# encoder.net
KiCad netlist of a schematic drawn in EAGLE
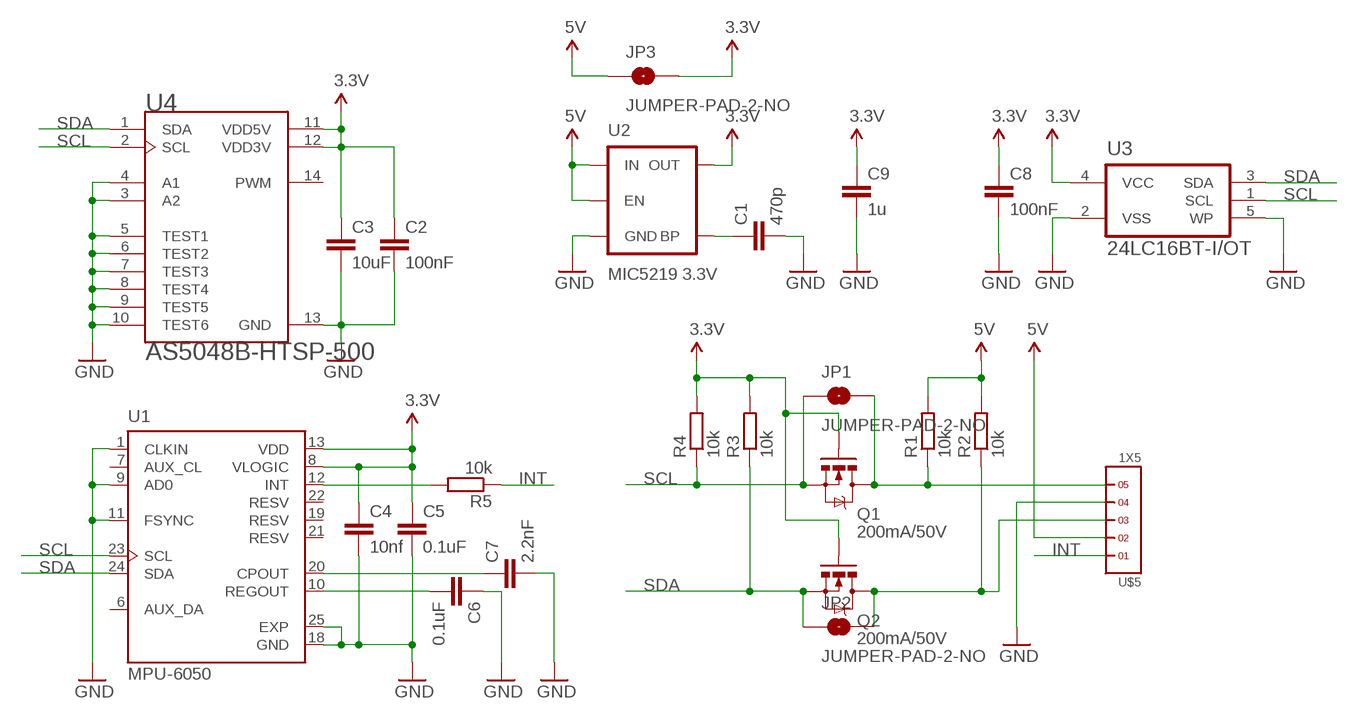
[diagram p0: schematic, sheet 1]

(export (version "E")
  (design (tool "Eeschema 10.0.6"))
  (components
    (comp (ref "C1")
      (value "470p")
      (footprint "eagle-import:C0402K")
      (libsource (lib "eagle-import") (part "C-EUC0402K"))
    )
    (comp (ref "C2")
      (value "100nF")
      (footprint "eagle-import:C0402K")
      (libsource (lib "eagle-import") (part "C-EUC0402K"))
    )
    (comp (ref "C3")
      (value "10uF")
      (footprint "eagle-import:C0603K")
      (libsource (lib "eagle-import") (part "C-EUC0603K"))
    )
    (comp (ref "C4")
      (value "10nf")
      (footprint "eagle-import:C0402K")
      (libsource (lib "eagle-import") (part "C-EUC0402K"))
    )
    (comp (ref "C5")
      (value "0.1uF")
      (footprint "eagle-import:C0402K")
      (libsource (lib "eagle-import") (part "C-EUC0402K"))
    )
    (comp (ref "C6")
      (value "0.1uF")
      (footprint "eagle-import:C0402K")
      (libsource (lib "eagle-import") (part "C-EUC0402K"))
    )
    (comp (ref "C7")
      (value "2.2nF")
      (footprint "eagle-import:C0402K")
      (libsource (lib "eagle-import") (part "C-EUC0402K"))
    )
    (comp (ref "C8")
      (value "100nF")
      (footprint "eagle-import:C0402K")
      (libsource (lib "eagle-import") (part "C-EUC0402K"))
    )
    (comp (ref "C9")
      (value "1u")
      (footprint "eagle-import:C0402K")
      (libsource (lib "eagle-import") (part "C-EUC0402K"))
    )
    (comp (ref "JP1")
      (value "JUMPER-PAD-2-NO")
      (footprint "eagle-import:PAD-JUMPER-2-NO_NO_SILK")
      (libsource (lib "eagle-import") (part "JUMPER-PAD-2-NO"))
    )
    (comp (ref "JP2")
      (value "JUMPER-PAD-2-NO")
      (footprint "eagle-import:PAD-JUMPER-2-NO_NO_SILK")
      (libsource (lib "eagle-import") (part "JUMPER-PAD-2-NO"))
    )
    (comp (ref "JP3")
      (value "JUMPER-PAD-2-NO")
      (footprint "eagle-import:PAD-JUMPER-2-NO_NO_SILK")
      (libsource (lib "eagle-import") (part "JUMPER-PAD-2-NO"))
    )
    (comp (ref "Q1")
      (value "200mA/50V")
      (footprint "eagle-import:SOT23-3")
      (libsource (lib "eagle-import") (part "MOSFET-NCHANNELBSS138"))
    )
    (comp (ref "Q2")
      (value "200mA/50V")
      (footprint "eagle-import:SOT23-3")
      (libsource (lib "eagle-import") (part "MOSFET-NCHANNELBSS138"))
    )
    (comp (ref "R1")
      (value "10k")
      (footprint "eagle-import:R0402")
      (libsource (lib "eagle-import") (part "R-EU_R0402"))
    )
    (comp (ref "R2")
      (value "10k")
      (footprint "eagle-import:R0402")
      (libsource (lib "eagle-import") (part "R-EU_R0402"))
    )
    (comp (ref "R3")
      (value "10k")
      (footprint "eagle-import:R0402")
      (libsource (lib "eagle-import") (part "R-EU_R0402"))
    )
    (comp (ref "R4")
      (value "10k")
      (footprint "eagle-import:R0402")
      (libsource (lib "eagle-import") (part "R-EU_R0402"))
    )
    (comp (ref "R5")
      (value "10k")
      (footprint "eagle-import:R0402")
      (libsource (lib "eagle-import") (part "R-EU_R0402"))
    )
    (comp (ref "U$5")
      (value "1X5")
      (footprint "eagle-import:1X5")
      (libsource (lib "eagle-import") (part "1X5"))
    )
    (comp (ref "U1")
      (value "MPU-6050")
      (footprint "eagle-import:QFN50P400X400X95-25N")
      (libsource (lib "eagle-import") (part "MPU-6050"))
    )
    (comp (ref "U2")
      (value "MIC5219 3.3V")
      (footprint "eagle-import:SOT23-5")
      (libsource (lib "eagle-import") (part "V_REG_MIC52193.3V"))
    )
    (comp (ref "U3")
      (value "24LC16BT-I/OT")
      (footprint "eagle-import:SOT-23-5")
      (libsource (lib "eagle-import") (part "24LC16BT-I/OT"))
    )
    (comp (ref "U4")
      (value "AS5048B-HTSP-500")
      (footprint "eagle-import:SOP65P640X120-14N")
      (libsource (lib "eagle-import") (part "AS5048B-HTSP-500"))
    )
  )
  (nets
    (net (code "1") (name "/INT") (class "Default")
      (node (ref "R5") (pin "1") (pinfunction "1_1") (pintype "passive"))
      (node (ref "U$5") (pin "1") (pinfunction "1_1") (pintype "bidirectional"))
    )
    (net (code "2") (name "/SCL") (class "Default")
      (node (ref "JP1") (pin "1") (pinfunction "1_1") (pintype "passive"))
      (node (ref "Q1") (pin "2") (pinfunction "S_2") (pintype "passive"))
      (node (ref "R4") (pin "1") (pinfunction "1_1") (pintype "passive"))
      (node (ref "U1") (pin "23") (pinfunction "SCL_23") (pintype "input"))
      (node (ref "U3") (pin "1") (pinfunction "SCL_1") (pintype "input"))
      (node (ref "U4") (pin "2") (pinfunction "SCL_2") (pintype "input"))
    )
    (net (code "3") (name "/SDA") (class "Default")
      (node (ref "JP2") (pin "1") (pinfunction "1_1") (pintype "passive"))
      (node (ref "Q2") (pin "2") (pinfunction "S_2") (pintype "passive"))
      (node (ref "R3") (pin "1") (pinfunction "1_1") (pintype "passive"))
      (node (ref "U1") (pin "24") (pinfunction "SDA_24") (pintype "bidirectional"))
      (node (ref "U3") (pin "3") (pinfunction "SDA_3") (pintype "bidirectional"))
      (node (ref "U4") (pin "1") (pinfunction "SDA_1") (pintype "input"))
    )
    (net (code "4") (name "3.3V") (class "Default")
      (node (ref "C2") (pin "1") (pinfunction "1_1") (pintype "passive"))
      (node (ref "C3") (pin "1") (pinfunction "1_1") (pintype "passive"))
      (node (ref "C4") (pin "1") (pinfunction "1_1") (pintype "passive"))
      (node (ref "C5") (pin "1") (pinfunction "1_1") (pintype "passive"))
      (node (ref "C8") (pin "1") (pinfunction "1_1") (pintype "passive"))
      (node (ref "C9") (pin "1") (pinfunction "1_1") (pintype "passive"))
      (node (ref "JP3") (pin "2") (pinfunction "2_2") (pintype "passive"))
      (node (ref "Q1") (pin "1") (pinfunction "G_1") (pintype "passive"))
      (node (ref "Q2") (pin "1") (pinfunction "G_1") (pintype "passive"))
      (node (ref "R3") (pin "2") (pinfunction "2_2") (pintype "passive"))
      (node (ref "R4") (pin "2") (pinfunction "2_2") (pintype "passive"))
      (node (ref "U1") (pin "13") (pinfunction "VDD_13") (pintype "power_in"))
      (node (ref "U1") (pin "8") (pinfunction "VLOGIC_8") (pintype "power_in"))
      (node (ref "U2") (pin "5") (pinfunction "OUT_5") (pintype "passive"))
      (node (ref "U3") (pin "4") (pinfunction "VCC_4") (pintype "power_in"))
      (node (ref "U4") (pin "11") (pinfunction "VDD5V_11") (pintype "power_in"))
      (node (ref "U4") (pin "12") (pinfunction "VDD3V_12") (pintype "power_in"))
    )
    (net (code "5") (name "5V") (class "Default")
      (node (ref "JP3") (pin "1") (pinfunction "1_1") (pintype "passive"))
      (node (ref "R1") (pin "2") (pinfunction "2_2") (pintype "passive"))
      (node (ref "R2") (pin "2") (pinfunction "2_2") (pintype "passive"))
      (node (ref "U$5") (pin "2") (pinfunction "2_2") (pintype "bidirectional"))
      (node (ref "U2") (pin "1") (pinfunction "IN_1") (pintype "input"))
      (node (ref "U2") (pin "3") (pinfunction "EN_3") (pintype "input"))
    )
    (net (code "6") (name "GND") (class "Default")
      (node (ref "C1") (pin "2") (pinfunction "2_2") (pintype "passive"))
      (node (ref "C2") (pin "2") (pinfunction "2_2") (pintype "passive"))
      (node (ref "C3") (pin "2") (pinfunction "2_2") (pintype "passive"))
      (node (ref "C4") (pin "2") (pinfunction "2_2") (pintype "passive"))
      (node (ref "C5") (pin "2") (pinfunction "2_2") (pintype "passive"))
      (node (ref "C6") (pin "1") (pinfunction "1_1") (pintype "passive"))
      (node (ref "C7") (pin "2") (pinfunction "2_2") (pintype "passive"))
      (node (ref "C8") (pin "2") (pinfunction "2_2") (pintype "passive"))
      (node (ref "C9") (pin "2") (pinfunction "2_2") (pintype "passive"))
      (node (ref "U$5") (pin "4") (pinfunction "4_4") (pintype "bidirectional"))
      (node (ref "U1") (pin "1") (pinfunction "CLKIN_1") (pintype "input"))
      (node (ref "U1") (pin "11") (pinfunction "FSYNC_11") (pintype "input"))
      (node (ref "U1") (pin "18") (pinfunction "GND_18") (pintype "power_in"))
      (node (ref "U1") (pin "25") (pinfunction "EXP_25") (pintype "power_in"))
      (node (ref "U1") (pin "9") (pinfunction "AD0_9") (pintype "input"))
      (node (ref "U2") (pin "2") (pinfunction "GND_2") (pintype "input"))
      (node (ref "U3") (pin "2") (pinfunction "VSS_2") (pintype "passive"))
      (node (ref "U3") (pin "5") (pinfunction "WP_5") (pintype "input"))
      (node (ref "U4") (pin "10") (pinfunction "TEST6_10") (pintype "bidirectional"))
      (node (ref "U4") (pin "13") (pinfunction "GND_13") (pintype "passive"))
      (node (ref "U4") (pin "3") (pinfunction "A2_3") (pintype "bidirectional"))
      (node (ref "U4") (pin "4") (pinfunction "A1_4") (pintype "input"))
      (node (ref "U4") (pin "5") (pinfunction "TEST1_5") (pintype "bidirectional"))
      (node (ref "U4") (pin "6") (pinfunction "TEST2_6") (pintype "bidirectional"))
      (node (ref "U4") (pin "7") (pinfunction "TEST3_7") (pintype "bidirectional"))
      (node (ref "U4") (pin "8") (pinfunction "TEST4_8") (pintype "bidirectional"))
      (node (ref "U4") (pin "9") (pinfunction "TEST5_9") (pintype "bidirectional"))
    )
    (net (code "7") (name "Net-(Q1-D)") (class "Default")
      (node (ref "JP1") (pin "2") (pinfunction "2_2") (pintype "passive"))
      (node (ref "Q1") (pin "3") (pinfunction "D_3") (pintype "passive"))
      (node (ref "R1") (pin "1") (pinfunction "1_1") (pintype "passive"))
      (node (ref "U$5") (pin "5") (pinfunction "5_5") (pintype "bidirectional"))
    )
    (net (code "8") (name "Net-(Q2-D)") (class "Default")
      (node (ref "JP2") (pin "2") (pinfunction "2_2") (pintype "passive"))
      (node (ref "Q2") (pin "3") (pinfunction "D_3") (pintype "passive"))
      (node (ref "R2") (pin "1") (pinfunction "1_1") (pintype "passive"))
      (node (ref "U$5") (pin "3") (pinfunction "3_3") (pintype "bidirectional"))
    )
    (net (code "9") (name "Net-(U1-CPOUT)") (class "Default")
      (node (ref "C7") (pin "1") (pinfunction "1_1") (pintype "passive"))
      (node (ref "U1") (pin "20") (pinfunction "CPOUT_20") (pintype "passive"))
    )
    (net (code "10") (name "Net-(U1-INT)") (class "Default")
      (node (ref "R5") (pin "2") (pinfunction "2_2") (pintype "passive"))
      (node (ref "U1") (pin "12") (pinfunction "INT_12") (pintype "output"))
    )
    (net (code "11") (name "Net-(U1-REGOUT)") (class "Default")
      (node (ref "C6") (pin "2") (pinfunction "2_2") (pintype "passive"))
      (node (ref "U1") (pin "10") (pinfunction "REGOUT_10") (pintype "passive"))
    )
    (net (code "12") (name "Net-(U2-BP)") (class "Default")
      (node (ref "C1") (pin "1") (pinfunction "1_1") (pintype "passive"))
      (node (ref "U2") (pin "4") (pinfunction "BP_4") (pintype "input"))
    )
    (net (code "13") (name "unconnected-(U1-AUX_CL-Pad7)") (class "Default")
      (node (ref "U1") (pin "7") (pinfunction "AUX_CL_7") (pintype "input"))
    )
    (net (code "14") (name "unconnected-(U1-AUX_DA-Pad6)") (class "Default")
      (node (ref "U1") (pin "6") (pinfunction "AUX_DA_6") (pintype "bidirectional"))
    )
    (net (code "15") (name "unconnected-(U1-RESV-Pad19)") (class "Default")
      (node (ref "U1") (pin "19") (pinfunction "RESV_19") (pintype "passive"))
    )
    (net (code "16") (name "unconnected-(U1-RESV-Pad21)") (class "Default")
      (node (ref "U1") (pin "21") (pinfunction "RESV_21") (pintype "passive"))
    )
    (net (code "17") (name "unconnected-(U1-RESV-Pad22)") (class "Default")
      (node (ref "U1") (pin "22") (pinfunction "RESV_22") (pintype "passive"))
    )
    (net (code "18") (name "unconnected-(U4-PWM-Pad14)") (class "Default")
      (node (ref "U4") (pin "14") (pinfunction "PWM_14") (pintype "output"))
    )
  )
)
